# KeDei_v6_2.net
KiCad netlist of a schematic drawn in EAGLE
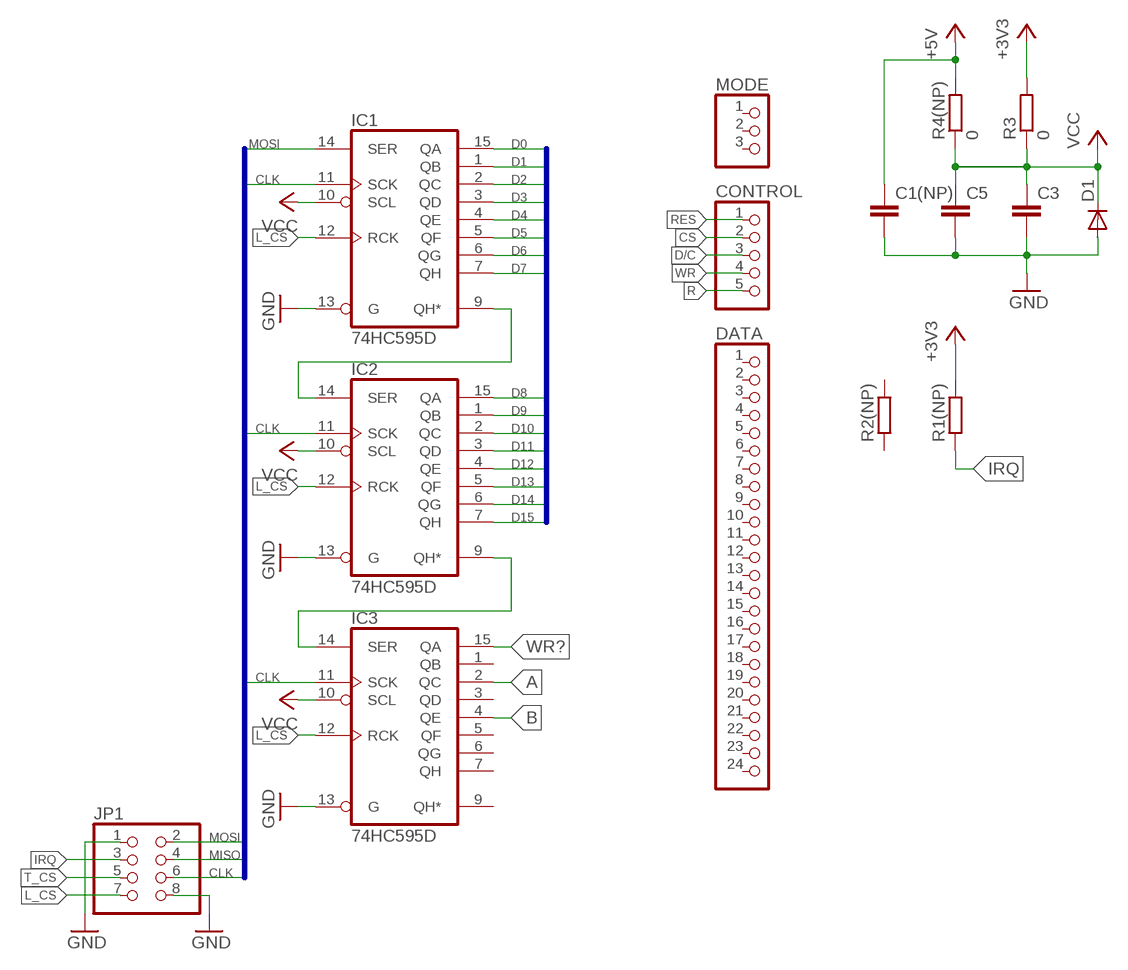
[diagram p0: schematic, sheet 1]

(export (version "E")
  (design (tool "Eeschema 10.0.6"))
  (components
    (comp (ref "C1(NP)")
      (value "C-EUC0603")
      (footprint "eagle-import:C0603")
      (libsource (lib "eagle-import") (part "C-EUC0603"))
    )
    (comp (ref "C3")
      (value "C-EUC0603")
      (footprint "eagle-import:C0603")
      (libsource (lib "eagle-import") (part "C-EUC0603"))
    )
    (comp (ref "C5")
      (value "C-EUC0603")
      (footprint "eagle-import:C0603")
      (libsource (lib "eagle-import") (part "C-EUC0603"))
    )
    (comp (ref "CONTROL")
      (value "PINHD-1X5")
      (footprint "eagle-import:1X05")
      (libsource (lib "eagle-import") (part "PINHD-1X5"))
    )
    (comp (ref "D1")
      (value "DIODE-MICROMELF-W")
      (footprint "eagle-import:MICROMELF-W")
      (libsource (lib "eagle-import") (part "DIODE-MICROMELF-W"))
    )
    (comp (ref "DATA")
      (value "PINHD-1X24")
      (footprint "eagle-import:1X24")
      (libsource (lib "eagle-import") (part "PINHD-1X24"))
    )
    (comp (ref "IC1")
      (value "74HC595D")
      (footprint "eagle-import:SO16")
      (libsource (lib "eagle-import") (part "74595DHC"))
    )
    (comp (ref "IC2")
      (value "74HC595D")
      (footprint "eagle-import:SO16")
      (libsource (lib "eagle-import") (part "74595DHC"))
    )
    (comp (ref "IC3")
      (value "74HC595D")
      (footprint "eagle-import:SO16")
      (libsource (lib "eagle-import") (part "74595DHC"))
    )
    (comp (ref "JP1")
      (value "PINHD-2X4")
      (footprint "eagle-import:2X04")
      (libsource (lib "eagle-import") (part "PINHD-2X4"))
    )
    (comp (ref "MODE")
      (value "PINHD-1X3")
      (footprint "eagle-import:1X03")
      (libsource (lib "eagle-import") (part "PINHD-1X3"))
    )
    (comp (ref "R1(NP)")
      (value "R-EU_R0603")
      (footprint "eagle-import:R0603")
      (libsource (lib "eagle-import") (part "R-EU_R0603"))
    )
    (comp (ref "R2(NP)")
      (value "R-EU_R0603")
      (footprint "eagle-import:R0603")
      (libsource (lib "eagle-import") (part "R-EU_R0603"))
    )
    (comp (ref "R3")
      (value "0")
      (footprint "eagle-import:R0603")
      (libsource (lib "eagle-import") (part "R-EU_R0603"))
    )
    (comp (ref "R4(NP)")
      (value "0")
      (footprint "eagle-import:R0603")
      (libsource (lib "eagle-import") (part "R-EU_R0603"))
    )
  )
  (nets
    (net (code "1") (name "+3V3") (class "Default")
      (node (ref "R1(NP)") (pin "2") (pinfunction "2_2") (pintype "passive"))
      (node (ref "R3") (pin "2") (pinfunction "2_2") (pintype "passive"))
    )
    (net (code "2") (name "+5V") (class "Default")
      (node (ref "C1(NP)") (pin "1") (pinfunction "1_1") (pintype "passive"))
      (node (ref "R4(NP)") (pin "2") (pinfunction "2_2") (pintype "passive"))
    )
    (net (code "3") (name "/CLK") (class "Default")
      (node (ref "IC1") (pin "11") (pinfunction "SCK_11") (pintype "input"))
      (node (ref "IC2") (pin "11") (pinfunction "SCK_11") (pintype "input"))
      (node (ref "IC3") (pin "11") (pinfunction "SCK_11") (pintype "input"))
      (node (ref "JP1") (pin "6") (pinfunction "6_6") (pintype "passive"))
    )
    (net (code "4") (name "/D0") (class "Default")
      (node (ref "IC1") (pin "15") (pinfunction "QA_15") (pintype "tri_state"))
    )
    (net (code "5") (name "/D1") (class "Default")
      (node (ref "IC1") (pin "1") (pinfunction "QB_1") (pintype "tri_state"))
    )
    (net (code "6") (name "/D2") (class "Default")
      (node (ref "IC1") (pin "2") (pinfunction "QC_2") (pintype "tri_state"))
    )
    (net (code "7") (name "/D3") (class "Default")
      (node (ref "IC1") (pin "3") (pinfunction "QD_3") (pintype "tri_state"))
    )
    (net (code "8") (name "/D4") (class "Default")
      (node (ref "IC1") (pin "4") (pinfunction "QE_4") (pintype "tri_state"))
    )
    (net (code "9") (name "/D5") (class "Default")
      (node (ref "IC1") (pin "5") (pinfunction "QF_5") (pintype "tri_state"))
    )
    (net (code "10") (name "/D6") (class "Default")
      (node (ref "IC1") (pin "6") (pinfunction "QG_6") (pintype "tri_state"))
    )
    (net (code "11") (name "/D7") (class "Default")
      (node (ref "IC1") (pin "7") (pinfunction "QH_7") (pintype "tri_state"))
    )
    (net (code "12") (name "/D8") (class "Default")
      (node (ref "IC2") (pin "15") (pinfunction "QA_15") (pintype "tri_state"))
    )
    (net (code "13") (name "/D9") (class "Default")
      (node (ref "IC2") (pin "1") (pinfunction "QB_1") (pintype "tri_state"))
    )
    (net (code "14") (name "/D10") (class "Default")
      (node (ref "IC2") (pin "2") (pinfunction "QC_2") (pintype "tri_state"))
    )
    (net (code "15") (name "/D11") (class "Default")
      (node (ref "IC2") (pin "3") (pinfunction "QD_3") (pintype "tri_state"))
    )
    (net (code "16") (name "/D12") (class "Default")
      (node (ref "IC2") (pin "4") (pinfunction "QE_4") (pintype "tri_state"))
    )
    (net (code "17") (name "/D13") (class "Default")
      (node (ref "IC2") (pin "5") (pinfunction "QF_5") (pintype "tri_state"))
    )
    (net (code "18") (name "/D14") (class "Default")
      (node (ref "IC2") (pin "6") (pinfunction "QG_6") (pintype "tri_state"))
    )
    (net (code "19") (name "/D15") (class "Default")
      (node (ref "IC2") (pin "7") (pinfunction "QH_7") (pintype "tri_state"))
    )
    (net (code "20") (name "/MISO") (class "Default")
      (node (ref "JP1") (pin "4") (pinfunction "4_4") (pintype "passive"))
    )
    (net (code "21") (name "/MOSI") (class "Default")
      (node (ref "IC1") (pin "14") (pinfunction "SER_14") (pintype "input"))
      (node (ref "JP1") (pin "2") (pinfunction "2_2") (pintype "passive"))
    )
    (net (code "22") (name "A") (class "Default")
      (node (ref "IC3") (pin "2") (pinfunction "QC_2") (pintype "tri_state"))
    )
    (net (code "23") (name "B") (class "Default")
      (node (ref "IC3") (pin "4") (pinfunction "QE_4") (pintype "tri_state"))
    )
    (net (code "24") (name "CS") (class "Default")
      (node (ref "CONTROL") (pin "2") (pinfunction "2_2") (pintype "passive"))
    )
    (net (code "25") (name "D{slash}C") (class "Default")
      (node (ref "CONTROL") (pin "3") (pinfunction "3_3") (pintype "passive"))
    )
    (net (code "26") (name "GND") (class "Default")
      (node (ref "C1(NP)") (pin "2") (pinfunction "2_2") (pintype "passive"))
      (node (ref "C3") (pin "2") (pinfunction "2_2") (pintype "passive"))
      (node (ref "C5") (pin "2") (pinfunction "2_2") (pintype "passive"))
      (node (ref "D1") (pin "A") (pinfunction "A_A") (pintype "passive"))
      (node (ref "IC1") (pin "13") (pinfunction "G_13") (pintype "input"))
      (node (ref "IC2") (pin "13") (pinfunction "G_13") (pintype "input"))
      (node (ref "IC3") (pin "13") (pinfunction "G_13") (pintype "input"))
      (node (ref "JP1") (pin "1") (pinfunction "1_1") (pintype "passive"))
      (node (ref "JP1") (pin "8") (pinfunction "8_8") (pintype "passive"))
    )
    (net (code "27") (name "IRQ") (class "Default")
      (node (ref "JP1") (pin "3") (pinfunction "3_3") (pintype "passive"))
      (node (ref "R1(NP)") (pin "1") (pinfunction "1_1") (pintype "passive"))
    )
    (net (code "28") (name "L_CS") (class "Default")
      (node (ref "IC1") (pin "12") (pinfunction "RCK_12") (pintype "input"))
      (node (ref "IC2") (pin "12") (pinfunction "RCK_12") (pintype "input"))
      (node (ref "IC3") (pin "12") (pinfunction "RCK_12") (pintype "input"))
      (node (ref "JP1") (pin "7") (pinfunction "7_7") (pintype "passive"))
    )
    (net (code "29") (name "Net-(IC1A-QH*)") (class "Default")
      (node (ref "IC1") (pin "9") (pinfunction "QH*_9") (pintype "tri_state"))
      (node (ref "IC2") (pin "14") (pinfunction "SER_14") (pintype "input"))
    )
    (net (code "30") (name "Net-(IC2A-QH*)") (class "Default")
      (node (ref "IC2") (pin "9") (pinfunction "QH*_9") (pintype "tri_state"))
      (node (ref "IC3") (pin "14") (pinfunction "SER_14") (pintype "input"))
    )
    (net (code "31") (name "R") (class "Default")
      (node (ref "CONTROL") (pin "5") (pinfunction "5_5") (pintype "passive"))
    )
    (net (code "32") (name "RES") (class "Default")
      (node (ref "CONTROL") (pin "1") (pinfunction "1_1") (pintype "passive"))
    )
    (net (code "33") (name "T_CS") (class "Default")
      (node (ref "JP1") (pin "5") (pinfunction "5_5") (pintype "passive"))
    )
    (net (code "34") (name "VCC") (class "Default")
      (node (ref "C3") (pin "1") (pinfunction "1_1") (pintype "passive"))
      (node (ref "C5") (pin "1") (pinfunction "1_1") (pintype "passive"))
      (node (ref "D1") (pin "C") (pinfunction "C_C") (pintype "passive"))
      (node (ref "IC1") (pin "10") (pinfunction "SCL_10") (pintype "input"))
      (node (ref "IC2") (pin "10") (pinfunction "SCL_10") (pintype "input"))
      (node (ref "IC3") (pin "10") (pinfunction "SCL_10") (pintype "input"))
      (node (ref "R3") (pin "1") (pinfunction "1_1") (pintype "passive"))
      (node (ref "R4(NP)") (pin "1") (pinfunction "1_1") (pintype "passive"))
    )
    (net (code "35") (name "WR") (class "Default")
      (node (ref "CONTROL") (pin "4") (pinfunction "4_4") (pintype "passive"))
    )
    (net (code "36") (name "WR?") (class "Default")
      (node (ref "IC3") (pin "15") (pinfunction "QA_15") (pintype "tri_state"))
    )
    (net (code "37") (name "unconnected-(DATA-Pad1)") (class "Default")
      (node (ref "DATA") (pin "1") (pinfunction "1_1") (pintype "passive"))
    )
    (net (code "38") (name "unconnected-(DATA-Pad2)") (class "Default")
      (node (ref "DATA") (pin "2") (pinfunction "2_2") (pintype "passive"))
    )
    (net (code "39") (name "unconnected-(DATA-Pad3)") (class "Default")
      (node (ref "DATA") (pin "3") (pinfunction "3_3") (pintype "passive"))
    )
    (net (code "40") (name "unconnected-(DATA-Pad4)") (class "Default")
      (node (ref "DATA") (pin "4") (pinfunction "4_4") (pintype "passive"))
    )
    (net (code "41") (name "unconnected-(DATA-Pad5)") (class "Default")
      (node (ref "DATA") (pin "5") (pinfunction "5_5") (pintype "passive"))
    )
    (net (code "42") (name "unconnected-(DATA-Pad6)") (class "Default")
      (node (ref "DATA") (pin "6") (pinfunction "6_6") (pintype "passive"))
    )
    (net (code "43") (name "unconnected-(DATA-Pad7)") (class "Default")
      (node (ref "DATA") (pin "7") (pinfunction "7_7") (pintype "passive"))
    )
    (net (code "44") (name "unconnected-(DATA-Pad8)") (class "Default")
      (node (ref "DATA") (pin "8") (pinfunction "8_8") (pintype "passive"))
    )
    (net (code "45") (name "unconnected-(DATA-Pad9)") (class "Default")
      (node (ref "DATA") (pin "9") (pinfunction "9_9") (pintype "passive"))
    )
    (net (code "46") (name "unconnected-(DATA-Pad10)") (class "Default")
      (node (ref "DATA") (pin "10") (pinfunction "10_10") (pintype "passive"))
    )
    (net (code "47") (name "unconnected-(DATA-Pad11)") (class "Default")
      (node (ref "DATA") (pin "11") (pinfunction "11_11") (pintype "passive"))
    )
    (net (code "48") (name "unconnected-(DATA-Pad12)") (class "Default")
      (node (ref "DATA") (pin "12") (pinfunction "12_12") (pintype "passive"))
    )
    (net (code "49") (name "unconnected-(DATA-Pad13)") (class "Default")
      (node (ref "DATA") (pin "13") (pinfunction "13_13") (pintype "passive"))
    )
    (net (code "50") (name "unconnected-(DATA-Pad14)") (class "Default")
      (node (ref "DATA") (pin "14") (pinfunction "14_14") (pintype "passive"))
    )
    (net (code "51") (name "unconnected-(DATA-Pad15)") (class "Default")
      (node (ref "DATA") (pin "15") (pinfunction "15_15") (pintype "passive"))
    )
    (net (code "52") (name "unconnected-(DATA-Pad16)") (class "Default")
      (node (ref "DATA") (pin "16") (pinfunction "16_16") (pintype "passive"))
    )
    (net (code "53") (name "unconnected-(DATA-Pad17)") (class "Default")
      (node (ref "DATA") (pin "17") (pinfunction "17_17") (pintype "passive"))
    )
    (net (code "54") (name "unconnected-(DATA-Pad18)") (class "Default")
      (node (ref "DATA") (pin "18") (pinfunction "18_18") (pintype "passive"))
    )
    (net (code "55") (name "unconnected-(DATA-Pad19)") (class "Default")
      (node (ref "DATA") (pin "19") (pinfunction "19_19") (pintype "passive"))
    )
    (net (code "56") (name "unconnected-(DATA-Pad20)") (class "Default")
      (node (ref "DATA") (pin "20") (pinfunction "20_20") (pintype "passive"))
    )
    (net (code "57") (name "unconnected-(DATA-Pad21)") (class "Default")
      (node (ref "DATA") (pin "21") (pinfunction "21_21") (pintype "passive"))
    )
    (net (code "58") (name "unconnected-(DATA-Pad22)") (class "Default")
      (node (ref "DATA") (pin "22") (pinfunction "22_22") (pintype "passive"))
    )
    (net (code "59") (name "unconnected-(DATA-Pad23)") (class "Default")
      (node (ref "DATA") (pin "23") (pinfunction "23_23") (pintype "passive"))
    )
    (net (code "60") (name "unconnected-(DATA-Pad24)") (class "Default")
      (node (ref "DATA") (pin "24") (pinfunction "24_24") (pintype "passive"))
    )
    (net (code "61") (name "unconnected-(IC3A-QB-Pad1)") (class "Default")
      (node (ref "IC3") (pin "1") (pinfunction "QB_1") (pintype "tri_state"))
    )
    (net (code "62") (name "unconnected-(IC3A-QD-Pad3)") (class "Default")
      (node (ref "IC3") (pin "3") (pinfunction "QD_3") (pintype "tri_state"))
    )
    (net (code "63") (name "unconnected-(IC3A-QF-Pad5)") (class "Default")
      (node (ref "IC3") (pin "5") (pinfunction "QF_5") (pintype "tri_state"))
    )
    (net (code "64") (name "unconnected-(IC3A-QG-Pad6)") (class "Default")
      (node (ref "IC3") (pin "6") (pinfunction "QG_6") (pintype "tri_state"))
    )
    (net (code "65") (name "unconnected-(IC3A-QH*-Pad9)") (class "Default")
      (node (ref "IC3") (pin "9") (pinfunction "QH*_9") (pintype "tri_state"))
    )
    (net (code "66") (name "unconnected-(IC3A-QH-Pad7)") (class "Default")
      (node (ref "IC3") (pin "7") (pinfunction "QH_7") (pintype "tri_state"))
    )
    (net (code "67") (name "unconnected-(MODE-Pad1)") (class "Default")
      (node (ref "MODE") (pin "1") (pinfunction "1_1") (pintype "passive"))
    )
    (net (code "68") (name "unconnected-(MODE-Pad2)") (class "Default")
      (node (ref "MODE") (pin "2") (pinfunction "2_2") (pintype "passive"))
    )
    (net (code "69") (name "unconnected-(MODE-Pad3)") (class "Default")
      (node (ref "MODE") (pin "3") (pinfunction "3_3") (pintype "passive"))
    )
    (net (code "70") (name "unconnected-(R2(NP)-Pad1)") (class "Default")
      (node (ref "R2(NP)") (pin "1") (pinfunction "1_1") (pintype "passive"))
    )
    (net (code "71") (name "unconnected-(R2(NP)-Pad2)") (class "Default")
      (node (ref "R2(NP)") (pin "2") (pinfunction "2_2") (pintype "passive"))
    )
  )
)
